# Connector_SOM240_2.net
KiCad netlist of a schematic drawn in Altium Designer
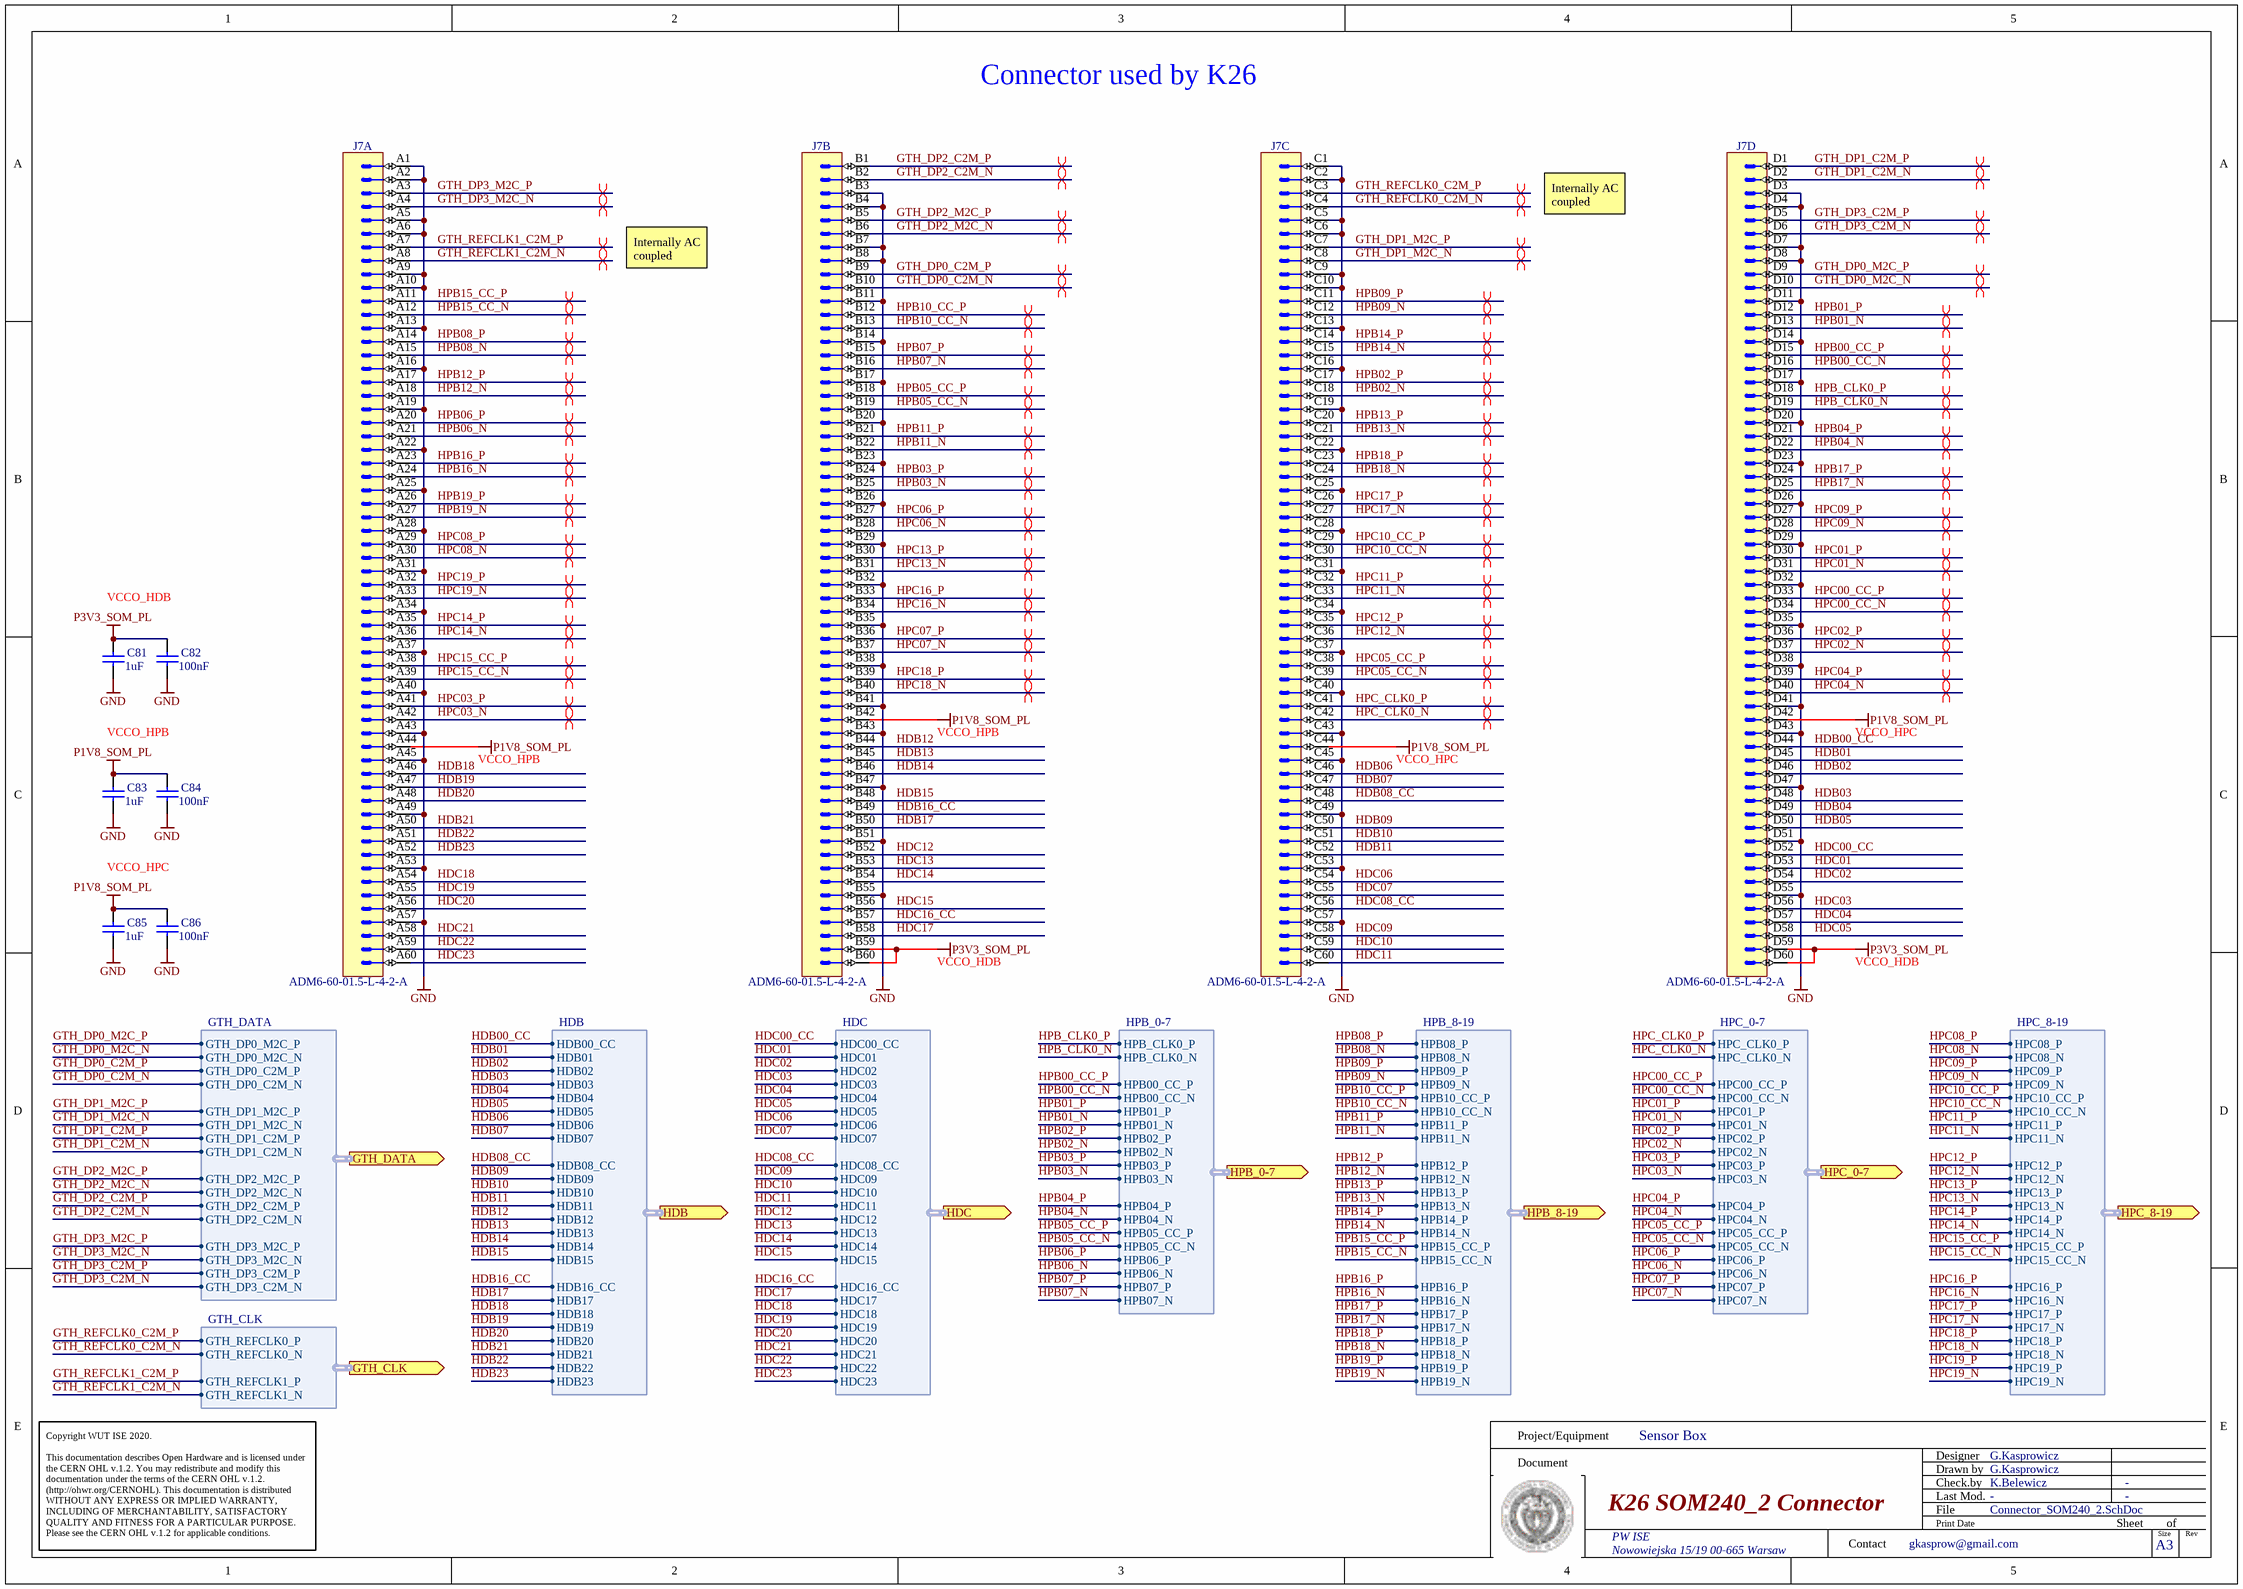
[diagram p0: Connector_SOM240_2.SchDoc]

(export (version "E")
  (design (tool "Eeschema 10.0.6"))
  (components
    (comp (ref "C81")
      (value "1uF")
      (footprint "CAPC1005X55N")
      (description "Non-polarised capacitor")
      (fields
        (field (name "PART NUMBER") "CC0402_1UF_16V_10%_X5R")
        (field (name "VOLTAGE") "16V")
        (field (name "AUTHOR") "CERN DEM JLC")
      )
      (libsource (lib "Capacitors") (part "Capacitor - non polarized"))
    )
    (comp (ref "C82")
      (value "100nF")
      (footprint "CAPC1005X55N")
      (description "Non-polarised capacitor")
      (fields
        (field (name "PART NUMBER") "CC0402_100NF_16V_10%_X5R")
        (field (name "VOLTAGE") "16V")
        (field (name "AUTHOR") "CERN DEM JLC")
      )
      (libsource (lib "Capacitors") (part "Capacitor - non polarized"))
    )
    (comp (ref "C83")
      (value "1uF")
      (footprint "CAPC1005X55N")
      (description "Non-polarised capacitor")
      (fields
        (field (name "PART NUMBER") "CC0402_1UF_16V_10%_X5R")
        (field (name "VOLTAGE") "16V")
        (field (name "AUTHOR") "CERN DEM JLC")
      )
      (libsource (lib "Capacitors") (part "Capacitor - non polarized"))
    )
    (comp (ref "C84")
      (value "100nF")
      (footprint "CAPC1005X55N")
      (description "Non-polarised capacitor")
      (fields
        (field (name "PART NUMBER") "CC0402_100NF_16V_10%_X5R")
        (field (name "VOLTAGE") "16V")
        (field (name "AUTHOR") "CERN DEM JLC")
      )
      (libsource (lib "Capacitors") (part "Capacitor - non polarized"))
    )
    (comp (ref "C85")
      (value "1uF")
      (footprint "CAPC1005X55N")
      (description "Non-polarised capacitor")
      (fields
        (field (name "PART NUMBER") "CC0402_1UF_16V_10%_X5R")
        (field (name "VOLTAGE") "16V")
        (field (name "AUTHOR") "CERN DEM JLC")
      )
      (libsource (lib "Capacitors") (part "Capacitor - non polarized"))
    )
    (comp (ref "C86")
      (value "100nF")
      (footprint "CAPC1005X55N")
      (description "Non-polarised capacitor")
      (fields
        (field (name "PART NUMBER") "CC0402_100NF_16V_10%_X5R")
        (field (name "VOLTAGE") "16V")
        (field (name "AUTHOR") "CERN DEM JLC")
      )
      (libsource (lib "Capacitors") (part "Capacitor - non polarized"))
    )
    (comp (ref "J7")
      (value "Header 240")
      (footprint "SAMTEC_ADM6-60-01.5-L-4-2-A")
      (description "Connector 240 Male contacts in 4 row abcd")
      (fields
        (field (name "PART NUMBER") "SAMTEC_ADM6-60-01.5-L-4-2-A")
        (field (name "MANUFACTURER") "SAMTEC")
        (field (name "MANUFACTURER PART NUMBER") "ADM6-60-01.5-L-4-2-A")
        (field (name "AUTHOR") "CERN DEM HF")
      )
      (libsource (lib "Connectors") (part "Connector 240 Male (4x60) (abcd)"))
    )
  )
  (nets
    (net (code "9") (name "/GTH_DP0_C2M_N") (class "Default")
      (node (ref "J7") (pin "B10") (pinfunction "B10_B10") (pintype "bidirectional"))
    )
    (net (code "10") (name "/GTH_DP0_C2M_P") (class "Default")
      (node (ref "J7") (pin "B9") (pinfunction "B9_B9") (pintype "bidirectional"))
    )
    (net (code "11") (name "/GTH_DP0_M2C_N") (class "Default")
      (node (ref "J7") (pin "D10") (pinfunction "D10_D10") (pintype "bidirectional"))
    )
    (net (code "12") (name "/GTH_DP0_M2C_P") (class "Default")
      (node (ref "J7") (pin "D9") (pinfunction "D9_D9") (pintype "bidirectional"))
    )
    (net (code "13") (name "/GTH_DP1_C2M_N") (class "Default")
      (node (ref "J7") (pin "D2") (pinfunction "D2_D2") (pintype "bidirectional"))
    )
    (net (code "14") (name "/GTH_DP1_C2M_P") (class "Default")
      (node (ref "J7") (pin "D1") (pinfunction "D1_D1") (pintype "bidirectional"))
    )
    (net (code "15") (name "/GTH_DP1_M2C_N") (class "Default")
      (node (ref "J7") (pin "C8") (pinfunction "C8_C8") (pintype "bidirectional"))
    )
    (net (code "16") (name "/GTH_DP1_M2C_P") (class "Default")
      (node (ref "J7") (pin "C7") (pinfunction "C7_C7") (pintype "bidirectional"))
    )
    (net (code "17") (name "/GTH_DP2_C2M_N") (class "Default")
      (node (ref "J7") (pin "B2") (pinfunction "B2_B2") (pintype "bidirectional"))
    )
    (net (code "18") (name "/GTH_DP2_C2M_P") (class "Default")
      (node (ref "J7") (pin "B1") (pinfunction "B1_B1") (pintype "bidirectional"))
    )
    (net (code "19") (name "/GTH_DP2_M2C_N") (class "Default")
      (node (ref "J7") (pin "B6") (pinfunction "B6_B6") (pintype "bidirectional"))
    )
    (net (code "20") (name "/GTH_DP2_M2C_P") (class "Default")
      (node (ref "J7") (pin "B5") (pinfunction "B5_B5") (pintype "bidirectional"))
    )
    (net (code "21") (name "/GTH_DP3_C2M_N") (class "Default")
      (node (ref "J7") (pin "D6") (pinfunction "D6_D6") (pintype "bidirectional"))
    )
    (net (code "22") (name "/GTH_DP3_C2M_P") (class "Default")
      (node (ref "J7") (pin "D5") (pinfunction "D5_D5") (pintype "bidirectional"))
    )
    (net (code "23") (name "/GTH_DP3_M2C_N") (class "Default")
      (node (ref "J7") (pin "A4") (pinfunction "A4_A4") (pintype "bidirectional"))
    )
    (net (code "24") (name "/GTH_DP3_M2C_P") (class "Default")
      (node (ref "J7") (pin "A3") (pinfunction "A3_A3") (pintype "bidirectional"))
    )
    (net (code "25") (name "/GTH_REFCLK0_C2M_N") (class "Default")
      (node (ref "J7") (pin "C4") (pinfunction "C4_C4") (pintype "bidirectional"))
    )
    (net (code "26") (name "/GTH_REFCLK0_C2M_P") (class "Default")
      (node (ref "J7") (pin "C3") (pinfunction "C3_C3") (pintype "bidirectional"))
    )
    (net (code "27") (name "/GTH_REFCLK1_C2M_N") (class "Default")
      (node (ref "J7") (pin "A8") (pinfunction "A8_A8") (pintype "bidirectional"))
    )
    (net (code "28") (name "/GTH_REFCLK1_C2M_P") (class "Default")
      (node (ref "J7") (pin "A7") (pinfunction "A7_A7") (pintype "bidirectional"))
    )
    (net (code "29") (name "/HDB00_CC") (class "Default")
      (node (ref "J7") (pin "D44") (pinfunction "D44_D44") (pintype "bidirectional"))
    )
    (net (code "30") (name "/HDB01") (class "Default")
      (node (ref "J7") (pin "D45") (pinfunction "D45_D45") (pintype "bidirectional"))
    )
    (net (code "31") (name "/HDB02") (class "Default")
      (node (ref "J7") (pin "D46") (pinfunction "D46_D46") (pintype "bidirectional"))
    )
    (net (code "32") (name "/HDB03") (class "Default")
      (node (ref "J7") (pin "D48") (pinfunction "D48_D48") (pintype "bidirectional"))
    )
    (net (code "33") (name "/HDB04") (class "Default")
      (node (ref "J7") (pin "D49") (pinfunction "D49_D49") (pintype "bidirectional"))
    )
    (net (code "34") (name "/HDB05") (class "Default")
      (node (ref "J7") (pin "D50") (pinfunction "D50_D50") (pintype "bidirectional"))
    )
    (net (code "35") (name "/HDB06") (class "Default")
      (node (ref "J7") (pin "C46") (pinfunction "C46_C46") (pintype "bidirectional"))
    )
    (net (code "36") (name "/HDB07") (class "Default")
      (node (ref "J7") (pin "C47") (pinfunction "C47_C47") (pintype "bidirectional"))
    )
    (net (code "37") (name "/HDB08_CC") (class "Default")
      (node (ref "J7") (pin "C48") (pinfunction "C48_C48") (pintype "bidirectional"))
    )
    (net (code "38") (name "/HDB09") (class "Default")
      (node (ref "J7") (pin "C50") (pinfunction "C50_C50") (pintype "bidirectional"))
    )
    (net (code "39") (name "/HDB10") (class "Default")
      (node (ref "J7") (pin "C51") (pinfunction "C51_C51") (pintype "bidirectional"))
    )
    (net (code "40") (name "/HDB11") (class "Default")
      (node (ref "J7") (pin "C52") (pinfunction "C52_C52") (pintype "bidirectional"))
    )
    (net (code "41") (name "/HDB12") (class "Default")
      (node (ref "J7") (pin "B44") (pinfunction "B44_B44") (pintype "bidirectional"))
    )
    (net (code "42") (name "/HDB13") (class "Default")
      (node (ref "J7") (pin "B45") (pinfunction "B45_B45") (pintype "bidirectional"))
    )
    (net (code "43") (name "/HDB14") (class "Default")
      (node (ref "J7") (pin "B46") (pinfunction "B46_B46") (pintype "bidirectional"))
    )
    (net (code "44") (name "/HDB15") (class "Default")
      (node (ref "J7") (pin "B48") (pinfunction "B48_B48") (pintype "bidirectional"))
    )
    (net (code "45") (name "/HDB16_CC") (class "Default")
      (node (ref "J7") (pin "B49") (pinfunction "B49_B49") (pintype "bidirectional"))
    )
    (net (code "46") (name "/HDB17") (class "Default")
      (node (ref "J7") (pin "B50") (pinfunction "B50_B50") (pintype "bidirectional"))
    )
    (net (code "47") (name "/HDB18") (class "Default")
      (node (ref "J7") (pin "A46") (pinfunction "A46_A46") (pintype "bidirectional"))
    )
    (net (code "48") (name "/HDB19") (class "Default")
      (node (ref "J7") (pin "A47") (pinfunction "A47_A47") (pintype "bidirectional"))
    )
    (net (code "49") (name "/HDB20") (class "Default")
      (node (ref "J7") (pin "A48") (pinfunction "A48_A48") (pintype "bidirectional"))
    )
    (net (code "50") (name "/HDB21") (class "Default")
      (node (ref "J7") (pin "A50") (pinfunction "A50_A50") (pintype "bidirectional"))
    )
    (net (code "51") (name "/HDB22") (class "Default")
      (node (ref "J7") (pin "A51") (pinfunction "A51_A51") (pintype "bidirectional"))
    )
    (net (code "52") (name "/HDB23") (class "Default")
      (node (ref "J7") (pin "A52") (pinfunction "A52_A52") (pintype "bidirectional"))
    )
    (net (code "53") (name "/HDC00_CC") (class "Default")
      (node (ref "J7") (pin "D52") (pinfunction "D52_D52") (pintype "bidirectional"))
    )
    (net (code "54") (name "/HDC01") (class "Default")
      (node (ref "J7") (pin "D53") (pinfunction "D53_D53") (pintype "bidirectional"))
    )
    (net (code "55") (name "/HDC02") (class "Default")
      (node (ref "J7") (pin "D54") (pinfunction "D54_D54") (pintype "bidirectional"))
    )
    (net (code "56") (name "/HDC03") (class "Default")
      (node (ref "J7") (pin "D56") (pinfunction "D56_D56") (pintype "bidirectional"))
    )
    (net (code "57") (name "/HDC04") (class "Default")
      (node (ref "J7") (pin "D57") (pinfunction "D57_D57") (pintype "bidirectional"))
    )
    (net (code "58") (name "/HDC05") (class "Default")
      (node (ref "J7") (pin "D58") (pinfunction "D58_D58") (pintype "bidirectional"))
    )
    (net (code "59") (name "/HDC06") (class "Default")
      (node (ref "J7") (pin "C54") (pinfunction "C54_C54") (pintype "bidirectional"))
    )
    (net (code "60") (name "/HDC07") (class "Default")
      (node (ref "J7") (pin "C55") (pinfunction "C55_C55") (pintype "bidirectional"))
    )
    (net (code "61") (name "/HDC08_CC") (class "Default")
      (node (ref "J7") (pin "C56") (pinfunction "C56_C56") (pintype "bidirectional"))
    )
    (net (code "62") (name "/HDC09") (class "Default")
      (node (ref "J7") (pin "C58") (pinfunction "C58_C58") (pintype "bidirectional"))
    )
    (net (code "63") (name "/HDC10") (class "Default")
      (node (ref "J7") (pin "C59") (pinfunction "C59_C59") (pintype "bidirectional"))
    )
    (net (code "64") (name "/HDC11") (class "Default")
      (node (ref "J7") (pin "C60") (pinfunction "C60_C60") (pintype "bidirectional"))
    )
    (net (code "65") (name "/HDC12") (class "Default")
      (node (ref "J7") (pin "B52") (pinfunction "B52_B52") (pintype "bidirectional"))
    )
    (net (code "66") (name "/HDC13") (class "Default")
      (node (ref "J7") (pin "B53") (pinfunction "B53_B53") (pintype "bidirectional"))
    )
    (net (code "67") (name "/HDC14") (class "Default")
      (node (ref "J7") (pin "B54") (pinfunction "B54_B54") (pintype "bidirectional"))
    )
    (net (code "68") (name "/HDC15") (class "Default")
      (node (ref "J7") (pin "B56") (pinfunction "B56_B56") (pintype "bidirectional"))
    )
    (net (code "69") (name "/HDC16_CC") (class "Default")
      (node (ref "J7") (pin "B57") (pinfunction "B57_B57") (pintype "bidirectional"))
    )
    (net (code "70") (name "/HDC17") (class "Default")
      (node (ref "J7") (pin "B58") (pinfunction "B58_B58") (pintype "bidirectional"))
    )
    (net (code "71") (name "/HDC18") (class "Default")
      (node (ref "J7") (pin "A54") (pinfunction "A54_A54") (pintype "bidirectional"))
    )
    (net (code "72") (name "/HDC19") (class "Default")
      (node (ref "J7") (pin "A55") (pinfunction "A55_A55") (pintype "bidirectional"))
    )
    (net (code "73") (name "/HDC20") (class "Default")
      (node (ref "J7") (pin "A56") (pinfunction "A56_A56") (pintype "bidirectional"))
    )
    (net (code "74") (name "/HDC21") (class "Default")
      (node (ref "J7") (pin "A58") (pinfunction "A58_A58") (pintype "bidirectional"))
    )
    (net (code "75") (name "/HDC22") (class "Default")
      (node (ref "J7") (pin "A59") (pinfunction "A59_A59") (pintype "bidirectional"))
    )
    (net (code "76") (name "/HDC23") (class "Default")
      (node (ref "J7") (pin "A60") (pinfunction "A60_A60") (pintype "bidirectional"))
    )
    (net (code "77") (name "/HPB00_CC_N") (class "Default")
      (node (ref "J7") (pin "D16") (pinfunction "D16_D16") (pintype "bidirectional"))
    )
    (net (code "78") (name "/HPB00_CC_P") (class "Default")
      (node (ref "J7") (pin "D15") (pinfunction "D15_D15") (pintype "bidirectional"))
    )
    (net (code "79") (name "/HPB01_N") (class "Default")
      (node (ref "J7") (pin "D13") (pinfunction "D13_D13") (pintype "bidirectional"))
    )
    (net (code "80") (name "/HPB01_P") (class "Default")
      (node (ref "J7") (pin "D12") (pinfunction "D12_D12") (pintype "bidirectional"))
    )
    (net (code "81") (name "/HPB02_N") (class "Default")
      (node (ref "J7") (pin "C18") (pinfunction "C18_C18") (pintype "bidirectional"))
    )
    (net (code "82") (name "/HPB02_P") (class "Default")
      (node (ref "J7") (pin "C17") (pinfunction "C17_C17") (pintype "bidirectional"))
    )
    (net (code "83") (name "/HPB03_N") (class "Default")
      (node (ref "J7") (pin "B25") (pinfunction "B25_B25") (pintype "bidirectional"))
    )
    (net (code "84") (name "/HPB03_P") (class "Default")
      (node (ref "J7") (pin "B24") (pinfunction "B24_B24") (pintype "bidirectional"))
    )
    (net (code "85") (name "/HPB04_N") (class "Default")
      (node (ref "J7") (pin "D22") (pinfunction "D22_D22") (pintype "bidirectional"))
    )
    (net (code "86") (name "/HPB04_P") (class "Default")
      (node (ref "J7") (pin "D21") (pinfunction "D21_D21") (pintype "bidirectional"))
    )
    (net (code "87") (name "/HPB05_CC_N") (class "Default")
      (node (ref "J7") (pin "B19") (pinfunction "B19_B19") (pintype "bidirectional"))
    )
    (net (code "88") (name "/HPB05_CC_P") (class "Default")
      (node (ref "J7") (pin "B18") (pinfunction "B18_B18") (pintype "bidirectional"))
    )
    (net (code "89") (name "/HPB06_N") (class "Default")
      (node (ref "J7") (pin "A21") (pinfunction "A21_A21") (pintype "bidirectional"))
    )
    (net (code "90") (name "/HPB06_P") (class "Default")
      (node (ref "J7") (pin "A20") (pinfunction "A20_A20") (pintype "bidirectional"))
    )
    (net (code "91") (name "/HPB07_N") (class "Default")
      (node (ref "J7") (pin "B16") (pinfunction "B16_B16") (pintype "bidirectional"))
    )
    (net (code "92") (name "/HPB07_P") (class "Default")
      (node (ref "J7") (pin "B15") (pinfunction "B15_B15") (pintype "bidirectional"))
    )
    (net (code "93") (name "/HPB08_N") (class "Default")
      (node (ref "J7") (pin "A15") (pinfunction "A15_A15") (pintype "bidirectional"))
    )
    (net (code "94") (name "/HPB08_P") (class "Default")
      (node (ref "J7") (pin "A14") (pinfunction "A14_A14") (pintype "bidirectional"))
    )
    (net (code "95") (name "/HPB09_N") (class "Default")
      (node (ref "J7") (pin "C12") (pinfunction "C12_C12") (pintype "bidirectional"))
    )
    (net (code "96") (name "/HPB09_P") (class "Default")
      (node (ref "J7") (pin "C11") (pinfunction "C11_C11") (pintype "bidirectional"))
    )
    (net (code "97") (name "/HPB10_CC_N") (class "Default")
      (node (ref "J7") (pin "B13") (pinfunction "B13_B13") (pintype "bidirectional"))
    )
    (net (code "98") (name "/HPB10_CC_P") (class "Default")
      (node (ref "J7") (pin "B12") (pinfunction "B12_B12") (pintype "bidirectional"))
    )
    (net (code "99") (name "/HPB11_N") (class "Default")
      (node (ref "J7") (pin "B22") (pinfunction "B22_B22") (pintype "bidirectional"))
    )
    (net (code "100") (name "/HPB11_P") (class "Default")
      (node (ref "J7") (pin "B21") (pinfunction "B21_B21") (pintype "bidirectional"))
    )
    (net (code "101") (name "/HPB12_N") (class "Default")
      (node (ref "J7") (pin "A18") (pinfunction "A18_A18") (pintype "bidirectional"))
    )
    (net (code "102") (name "/HPB12_P") (class "Default")
      (node (ref "J7") (pin "A17") (pinfunction "A17_A17") (pintype "bidirectional"))
    )
    (net (code "103") (name "/HPB13_N") (class "Default")
      (node (ref "J7") (pin "C21") (pinfunction "C21_C21") (pintype "bidirectional"))
    )
    (net (code "104") (name "/HPB13_P") (class "Default")
      (node (ref "J7") (pin "C20") (pinfunction "C20_C20") (pintype "bidirectional"))
    )
    (net (code "105") (name "/HPB14_N") (class "Default")
      (node (ref "J7") (pin "C15") (pinfunction "C15_C15") (pintype "bidirectional"))
    )
    (net (code "106") (name "/HPB14_P") (class "Default")
      (node (ref "J7") (pin "C14") (pinfunction "C14_C14") (pintype "bidirectional"))
    )
    (net (code "107") (name "/HPB15_CC_N") (class "Default")
      (node (ref "J7") (pin "A12") (pinfunction "A12_A12") (pintype "bidirectional"))
    )
    (net (code "108") (name "/HPB15_CC_P") (class "Default")
      (node (ref "J7") (pin "A11") (pinfunction "A11_A11") (pintype "bidirectional"))
    )
    (net (code "109") (name "/HPB16_N") (class "Default")
      (node (ref "J7") (pin "A24") (pinfunction "A24_A24") (pintype "bidirectional"))
    )
    (net (code "110") (name "/HPB16_P") (class "Default")
      (node (ref "J7") (pin "A23") (pinfunction "A23_A23") (pintype "bidirectional"))
    )
    (net (code "111") (name "/HPB17_N") (class "Default")
      (node (ref "J7") (pin "D25") (pinfunction "D25_D25") (pintype "bidirectional"))
    )
    (net (code "112") (name "/HPB17_P") (class "Default")
      (node (ref "J7") (pin "D24") (pinfunction "D24_D24") (pintype "bidirectional"))
    )
    (net (code "113") (name "/HPB18_N") (class "Default")
      (node (ref "J7") (pin "C24") (pinfunction "C24_C24") (pintype "bidirectional"))
    )
    (net (code "114") (name "/HPB18_P") (class "Default")
      (node (ref "J7") (pin "C23") (pinfunction "C23_C23") (pintype "bidirectional"))
    )
    (net (code "115") (name "/HPB19_N") (class "Default")
      (node (ref "J7") (pin "A27") (pinfunction "A27_A27") (pintype "bidirectional"))
    )
    (net (code "116") (name "/HPB19_P") (class "Default")
      (node (ref "J7") (pin "A26") (pinfunction "A26_A26") (pintype "bidirectional"))
    )
    (net (code "117") (name "/HPB_CLK0_N") (class "Default")
      (node (ref "J7") (pin "D19") (pinfunction "D19_D19") (pintype "bidirectional"))
    )
    (net (code "118") (name "/HPB_CLK0_P") (class "Default")
      (node (ref "J7") (pin "D18") (pinfunction "D18_D18") (pintype "bidirectional"))
    )
    (net (code "119") (name "/HPC00_CC_N") (class "Default")
      (node (ref "J7") (pin "D34") (pinfunction "D34_D34") (pintype "bidirectional"))
    )
    (net (code "120") (name "/HPC00_CC_P") (class "Default")
      (node (ref "J7") (pin "D33") (pinfunction "D33_D33") (pintype "bidirectional"))
    )
    (net (code "121") (name "/HPC01_N") (class "Default")
      (node (ref "J7") (pin "D31") (pinfunction "D31_D31") (pintype "bidirectional"))
    )
    (net (code "122") (name "/HPC01_P") (class "Default")
      (node (ref "J7") (pin "D30") (pinfunction "D30_D30") (pintype "bidirectional"))
    )
    (net (code "123") (name "/HPC02_N") (class "Default")
      (node (ref "J7") (pin "D37") (pinfunction "D37_D37") (pintype "bidirectional"))
    )
    (net (code "124") (name "/HPC02_P") (class "Default")
      (node (ref "J7") (pin "D36") (pinfunction "D36_D36") (pintype "bidirectional"))
    )
    (net (code "125") (name "/HPC03_N") (class "Default")
      (node (ref "J7") (pin "A42") (pinfunction "A42_A42") (pintype "bidirectional"))
    )
    (net (code "126") (name "/HPC03_P") (class "Default")
      (node (ref "J7") (pin "A41") (pinfunction "A41_A41") (pintype "bidirectional"))
    )
    (net (code "127") (name "/HPC04_N") (class "Default")
      (node (ref "J7") (pin "D40") (pinfunction "D40_D40") (pintype "bidirectional"))
    )
    (net (code "128") (name "/HPC04_P") (class "Default")
      (node (ref "J7") (pin "D39") (pinfunction "D39_D39") (pintype "bidirectional"))
    )
    (net (code "129") (name "/HPC05_CC_N") (class "Default")
      (node (ref "J7") (pin "C39") (pinfunction "C39_C39") (pintype "bidirectional"))
    )
    (net (code "130") (name "/HPC05_CC_P") (class "Default")
      (node (ref "J7") (pin "C38") (pinfunction "C38_C38") (pintype "bidirectional"))
    )
    (net (code "131") (name "/HPC06_N") (class "Default")
      (node (ref "J7") (pin "B28") (pinfunction "B28_B28") (pintype "bidirectional"))
    )
    (net (code "132") (name "/HPC06_P") (class "Default")
      (node (ref "J7") (pin "B27") (pinfunction "B27_B27") (pintype "bidirectional"))
    )
    (net (code "133") (name "/HPC07_N") (class "Default")
      (node (ref "J7") (pin "B37") (pinfunction "B37_B37") (pintype "bidirectional"))
    )
    (net (code "134") (name "/HPC07_P") (class "Default")
      (node (ref "J7") (pin "B36") (pinfunction "B36_B36") (pintype "bidirectional"))
    )
    (net (code "135") (name "/HPC08_N") (class "Default")
      (node (ref "J7") (pin "A30") (pinfunction "A30_A30") (pintype "bidirectional"))
    )
    (net (code "136") (name "/HPC08_P") (class "Default")
      (node (ref "J7") (pin "A29") (pinfunction "A29_A29") (pintype "bidirectional"))
    )
    (net (code "137") (name "/HPC09_N") (class "Default")
      (node (ref "J7") (pin "D28") (pinfunction "D28_D28") (pintype "bidirectional"))
    )
    (net (code "138") (name "/HPC09_P") (class "Default")
      (node (ref "J7") (pin "D27") (pinfunction "D27_D27") (pintype "bidirectional"))
    )
    (net (code "139") (name "/HPC10_CC_N") (class "Default")
      (node (ref "J7") (pin "C30") (pinfunction "C30_C30") (pintype "bidirectional"))
    )
    (net (code "140") (name "/HPC10_CC_P") (class "Default")
      (node (ref "J7") (pin "C29") (pinfunction "C29_C29") (pintype "bidirectional"))
    )
    (net (code "141") (name "/HPC11_N") (class "Default")
      (node (ref "J7") (pin "C33") (pinfunction "C33_C33") (pintype "bidirectional"))
    )
    (net (code "142") (name "/HPC11_P") (class "Default")
      (node (ref "J7") (pin "C32") (pinfunction "C32_C32") (pintype "bidirectional"))
    )
    (net (code "143") (name "/HPC12_N") (class "Default")
      (node (ref "J7") (pin "C36") (pinfunction "C36_C36") (pintype "bidirectional"))
    )
    (net (code "144") (name "/HPC12_P") (class "Default")
      (node (ref "J7") (pin "C35") (pinfunction "C35_C35") (pintype "bidirectional"))
    )
    (net (code "145") (name "/HPC13_N") (class "Default")
      (node (ref "J7") (pin "B31") (pinfunction "B31_B31") (pintype "bidirectional"))
    )
    (net (code "146") (name "/HPC13_P") (class "Default")
      (node (ref "J7") (pin "B30") (pinfunction "B30_B30") (pintype "bidirectional"))
    )
    (net (code "147") (name "/HPC14_N") (class "Default")
      (node (ref "J7") (pin "A36") (pinfunction "A36_A36") (pintype "bidirectional"))
    )
    (net (code "148") (name "/HPC14_P") (class "Default")
      (node (ref "J7") (pin "A35") (pinfunction "A35_A35") (pintype "bidirectional"))
    )
    (net (code "149") (name "/HPC15_CC_N") (class "Default")
      (node (ref "J7") (pin "A39") (pinfunction "A39_A39") (pintype "bidirectional"))
    )
    (net (code "150") (name "/HPC15_CC_P") (class "Default")
      (node (ref "J7") (pin "A38") (pinfunction "A38_A38") (pintype "bidirectional"))
    )
    (net (code "151") (name "/HPC16_N") (class "Default")
      (node (ref "J7") (pin "B34") (pinfunction "B34_B34") (pintype "bidirectional"))
    )
    (net (code "152") (name "/HPC16_P") (class "Default")
      (node (ref "J7") (pin "B33") (pinfunction "B33_B33") (pintype "bidirectional"))
    )
    (net (code "153") (name "/HPC17_N") (class "Default")
      (node (ref "J7") (pin "C27") (pinfunction "C27_C27") (pintype "bidirectional"))
    )
    (net (code "154") (name "/HPC17_P") (class "Default")
      (node (ref "J7") (pin "C26") (pinfunction "C26_C26") (pintype "bidirectional"))
    )
    (net (code "155") (name "/HPC18_N") (class "Default")
      (node (ref "J7") (pin "B40") (pinfunction "B40_B40") (pintype "bidirectional"))
    )
    (net (code "156") (name "/HPC18_P") (class "Default")
      (node (ref "J7") (pin "B39") (pinfunction "B39_B39") (pintype "bidirectional"))
    )
    (net (code "157") (name "/HPC19_N") (class "Default")
      (node (ref "J7") (pin "A33") (pinfunction "A33_A33") (pintype "bidirectional"))
    )
    (net (code "158") (name "/HPC19_P") (class "Default")
      (node (ref "J7") (pin "A32") (pinfunction "A32_A32") (pintype "bidirectional"))
    )
    (net (code "159") (name "/HPC_CLK0_N") (class "Default")
      (node (ref "J7") (pin "C42") (pinfunction "C42_C42") (pintype "bidirectional"))
    )
    (net (code "160") (name "/HPC_CLK0_P") (class "Default")
      (node (ref "J7") (pin "C41") (pinfunction "C41_C41") (pintype "bidirectional"))
    )
    (net (code "169") (name "GND") (class "Default")
      (node (ref "C81") (pin "1") (pinfunction "1_1") (pintype "passive"))
      (node (ref "C82") (pin "1") (pinfunction "1_1") (pintype "passive"))
      (node (ref "C83") (pin "1") (pinfunction "1_1") (pintype "passive"))
      (node (ref "C84") (pin "1") (pinfunction "1_1") (pintype "passive"))
      (node (ref "C85") (pin "1") (pinfunction "1_1") (pintype "passive"))
      (node (ref "C86") (pin "1") (pinfunction "1_1") (pintype "passive"))
      (node (ref "J7") (pin "A1") (pinfunction "A1_A1") (pintype "bidirectional"))
      (node (ref "J7") (pin "A10") (pinfunction "A10_A10") (pintype "bidirectional"))
      (node (ref "J7") (pin "A13") (pinfunction "A13_A13") (pintype "bidirectional"))
      (node (ref "J7") (pin "A16") (pinfunction "A16_A16") (pintype "bidirectional"))
      (node (ref "J7") (pin "A19") (pinfunction "A19_A19") (pintype "bidirectional"))
      (node (ref "J7") (pin "A2") (pinfunction "A2_A2") (pintype "bidirectional"))
      (node (ref "J7") (pin "A22") (pinfunction "A22_A22") (pintype "bidirectional"))
      (node (ref "J7") (pin "A25") (pinfunction "A25_A25") (pintype "bidirectional"))
      (node (ref "J7") (pin "A28") (pinfunction "A28_A28") (pintype "bidirectional"))
      (node (ref "J7") (pin "A31") (pinfunction "A31_A31") (pintype "bidirectional"))
      (node (ref "J7") (pin "A34") (pinfunction "A34_A34") (pintype "bidirectional"))
      (node (ref "J7") (pin "A37") (pinfunction "A37_A37") (pintype "bidirectional"))
      (node (ref "J7") (pin "A40") (pinfunction "A40_A40") (pintype "bidirectional"))
      (node (ref "J7") (pin "A43") (pinfunction "A43_A43") (pintype "bidirectional"))
      (node (ref "J7") (pin "A45") (pinfunction "A45_A45") (pintype "bidirectional"))
      (node (ref "J7") (pin "A49") (pinfunction "A49_A49") (pintype "bidirectional"))
      (node (ref "J7") (pin "A5") (pinfunction "A5_A5") (pintype "bidirectional"))
      (node (ref "J7") (pin "A53") (pinfunction "A53_A53") (pintype "bidirectional"))
      (node (ref "J7") (pin "A57") (pinfunction "A57_A57") (pintype "bidirectional"))
      (node (ref "J7") (pin "A6") (pinfunction "A6_A6") (pintype "bidirectional"))
      (node (ref "J7") (pin "A9") (pinfunction "A9_A9") (pintype "bidirectional"))
      (node (ref "J7") (pin "B11") (pinfunction "B11_B11") (pintype "bidirectional"))
      (node (ref "J7") (pin "B14") (pinfunction "B14_B14") (pintype "bidirectional"))
      (node (ref "J7") (pin "B17") (pinfunction "B17_B17") (pintype "bidirectional"))
      (node (ref "J7") (pin "B20") (pinfunction "B20_B20") (pintype "bidirectional"))
      (node (ref "J7") (pin "B23") (pinfunction "B23_B23") (pintype "bidirectional"))
      (node (ref "J7") (pin "B26") (pinfunction "B26_B26") (pintype "bidirectional"))
      (node (ref "J7") (pin "B29") (pinfunction "B29_B29") (pintype "bidirectional"))
      (node (ref "J7") (pin "B3") (pinfunction "B3_B3") (pintype "bidirectional"))
      (node (ref "J7") (pin "B32") (pinfunction "B32_B32") (pintype "bidirectional"))
      (node (ref "J7") (pin "B35") (pinfunction "B35_B35") (pintype "bidirectional"))
      (node (ref "J7") (pin "B38") (pinfunction "B38_B38") (pintype "bidirectional"))
      (node (ref "J7") (pin "B4") (pinfunction "B4_B4") (pintype "bidirectional"))
      (node (ref "J7") (pin "B41") (pinfunction "B41_B41") (pintype "bidirectional"))
      (node (ref "J7") (pin "B43") (pinfunction "B43_B43") (pintype "bidirectional"))
      (node (ref "J7") (pin "B47") (pinfunction "B47_B47") (pintype "bidirectional"))
      (node (ref "J7") (pin "B51") (pinfunction "B51_B51") (pintype "bidirectional"))
      (node (ref "J7") (pin "B55") (pinfunction "B55_B55") (pintype "bidirectional"))
      (node (ref "J7") (pin "B7") (pinfunction "B7_B7") (pintype "bidirectional"))
      (node (ref "J7") (pin "B8") (pinfunction "B8_B8") (pintype "bidirectional"))
      (node (ref "J7") (pin "C1") (pinfunction "C1_C1") (pintype "bidirectional"))
      (node (ref "J7") (pin "C10") (pinfunction "C10_C10") (pintype "bidirectional"))
      (node (ref "J7") (pin "C13") (pinfunction "C13_C13") (pintype "bidirectional"))
      (node (ref "J7") (pin "C16") (pinfunction "C16_C16") (pintype "bidirectional"))
      (node (ref "J7") (pin "C19") (pinfunction "C19_C19") (pintype "bidirectional"))
      (node (ref "J7") (pin "C2") (pinfunction "C2_C2") (pintype "bidirectional"))
      (node (ref "J7") (pin "C22") (pinfunction "C22_C22") (pintype "bidirectional"))
      (node (ref "J7") (pin "C25") (pinfunction "C25_C25") (pintype "bidirectional"))
      (node (ref "J7") (pin "C28") (pinfunction "C28_C28") (pintype "bidirectional"))
      (node (ref "J7") (pin "C31") (pinfunction "C31_C31") (pintype "bidirectional"))
      (node (ref "J7") (pin "C34") (pinfunction "C34_C34") (pintype "bidirectional"))
      (node (ref "J7") (pin "C37") (pinfunction "C37_C37") (pintype "bidirectional"))
      (node (ref "J7") (pin "C40") (pinfunction "C40_C40") (pintype "bidirectional"))
      (node (ref "J7") (pin "C43") (pinfunction "C43_C43") (pintype "bidirectional"))
      (node (ref "J7") (pin "C45") (pinfunction "C45_C45") (pintype "bidirectional"))
      (node (ref "J7") (pin "C49") (pinfunction "C49_C49") (pintype "bidirectional"))
      (node (ref "J7") (pin "C5") (pinfunction "C5_C5") (pintype "bidirectional"))
      (node (ref "J7") (pin "C53") (pinfunction "C53_C53") (pintype "bidirectional"))
      (node (ref "J7") (pin "C57") (pinfunction "C57_C57") (pintype "bidirectional"))
      (node (ref "J7") (pin "C6") (pinfunction "C6_C6") (pintype "bidirectional"))
      (node (ref "J7") (pin "C9") (pinfunction "C9_C9") (pintype "bidirectional"))
      (node (ref "J7") (pin "D11") (pinfunction "D11_D11") (pintype "bidirectional"))
      (node (ref "J7") (pin "D14") (pinfunction "D14_D14") (pintype "bidirectional"))
      (node (ref "J7") (pin "D17") (pinfunction "D17_D17") (pintype "bidirectional"))
      (node (ref "J7") (pin "D20") (pinfunction "D20_D20") (pintype "bidirectional"))
      (node (ref "J7") (pin "D23") (pinfunction "D23_D23") (pintype "bidirectional"))
      (node (ref "J7") (pin "D26") (pinfunction "D26_D26") (pintype "bidirectional"))
      (node (ref "J7") (pin "D29") (pinfunction "D29_D29") (pintype "bidirectional"))
      (node (ref "J7") (pin "D3") (pinfunction "D3_D3") (pintype "bidirectional"))
      (node (ref "J7") (pin "D32") (pinfunction "D32_D32") (pintype "bidirectional"))
      (node (ref "J7") (pin "D35") (pinfunction "D35_D35") (pintype "bidirectional"))
      (node (ref "J7") (pin "D38") (pinfunction "D38_D38") (pintype "bidirectional"))
      (node (ref "J7") (pin "D4") (pinfunction "D4_D4") (pintype "bidirectional"))
      (node (ref "J7") (pin "D41") (pinfunction "D41_D41") (pintype "bidirectional"))
      (node (ref "J7") (pin "D43") (pinfunction "D43_D43") (pintype "bidirectional"))
      (node (ref "J7") (pin "D47") (pinfunction "D47_D47") (pintype "bidirectional"))
      (node (ref "J7") (pin "D51") (pinfunction "D51_D51") (pintype "bidirectional"))
      (node (ref "J7") (pin "D55") (pinfunction "D55_D55") (pintype "bidirectional"))
      (node (ref "J7") (pin "D7") (pinfunction "D7_D7") (pintype "bidirectional"))
      (node (ref "J7") (pin "D8") (pinfunction "D8_D8") (pintype "bidirectional"))
    )
    (net (code "170") (name "P1V8_SOM_PL") (class "Default")
      (node (ref "C83") (pin "2") (pinfunction "2_2") (pintype "passive"))
      (node (ref "C84") (pin "2") (pinfunction "2_2") (pintype "passive"))
      (node (ref "C85") (pin "2") (pinfunction "2_2") (pintype "passive"))
      (node (ref "C86") (pin "2") (pinfunction "2_2") (pintype "passive"))
      (node (ref "J7") (pin "A44") (pinfunction "A44_A44") (pintype "bidirectional"))
      (node (ref "J7") (pin "B42") (pinfunction "B42_B42") (pintype "bidirectional"))
      (node (ref "J7") (pin "C44") (pinfunction "C44_C44") (pintype "bidirectional"))
      (node (ref "J7") (pin "D42") (pinfunction "D42_D42") (pintype "bidirectional"))
    )
    (net (code "171") (name "P3V3_SOM_PL") (class "Default")
      (node (ref "C81") (pin "2") (pinfunction "2_2") (pintype "passive"))
      (node (ref "C82") (pin "2") (pinfunction "2_2") (pintype "passive"))
      (node (ref "J7") (pin "B59") (pinfunction "B59_B59") (pintype "bidirectional"))
      (node (ref "J7") (pin "B60") (pinfunction "B60_B60") (pintype "bidirectional"))
      (node (ref "J7") (pin "D59") (pinfunction "D59_D59") (pintype "bidirectional"))
      (node (ref "J7") (pin "D60") (pinfunction "D60_D60") (pintype "bidirectional"))
    )
  )
)
